# 15_ETHERNET.net
KiCad netlist of a schematic drawn in Altium Designer
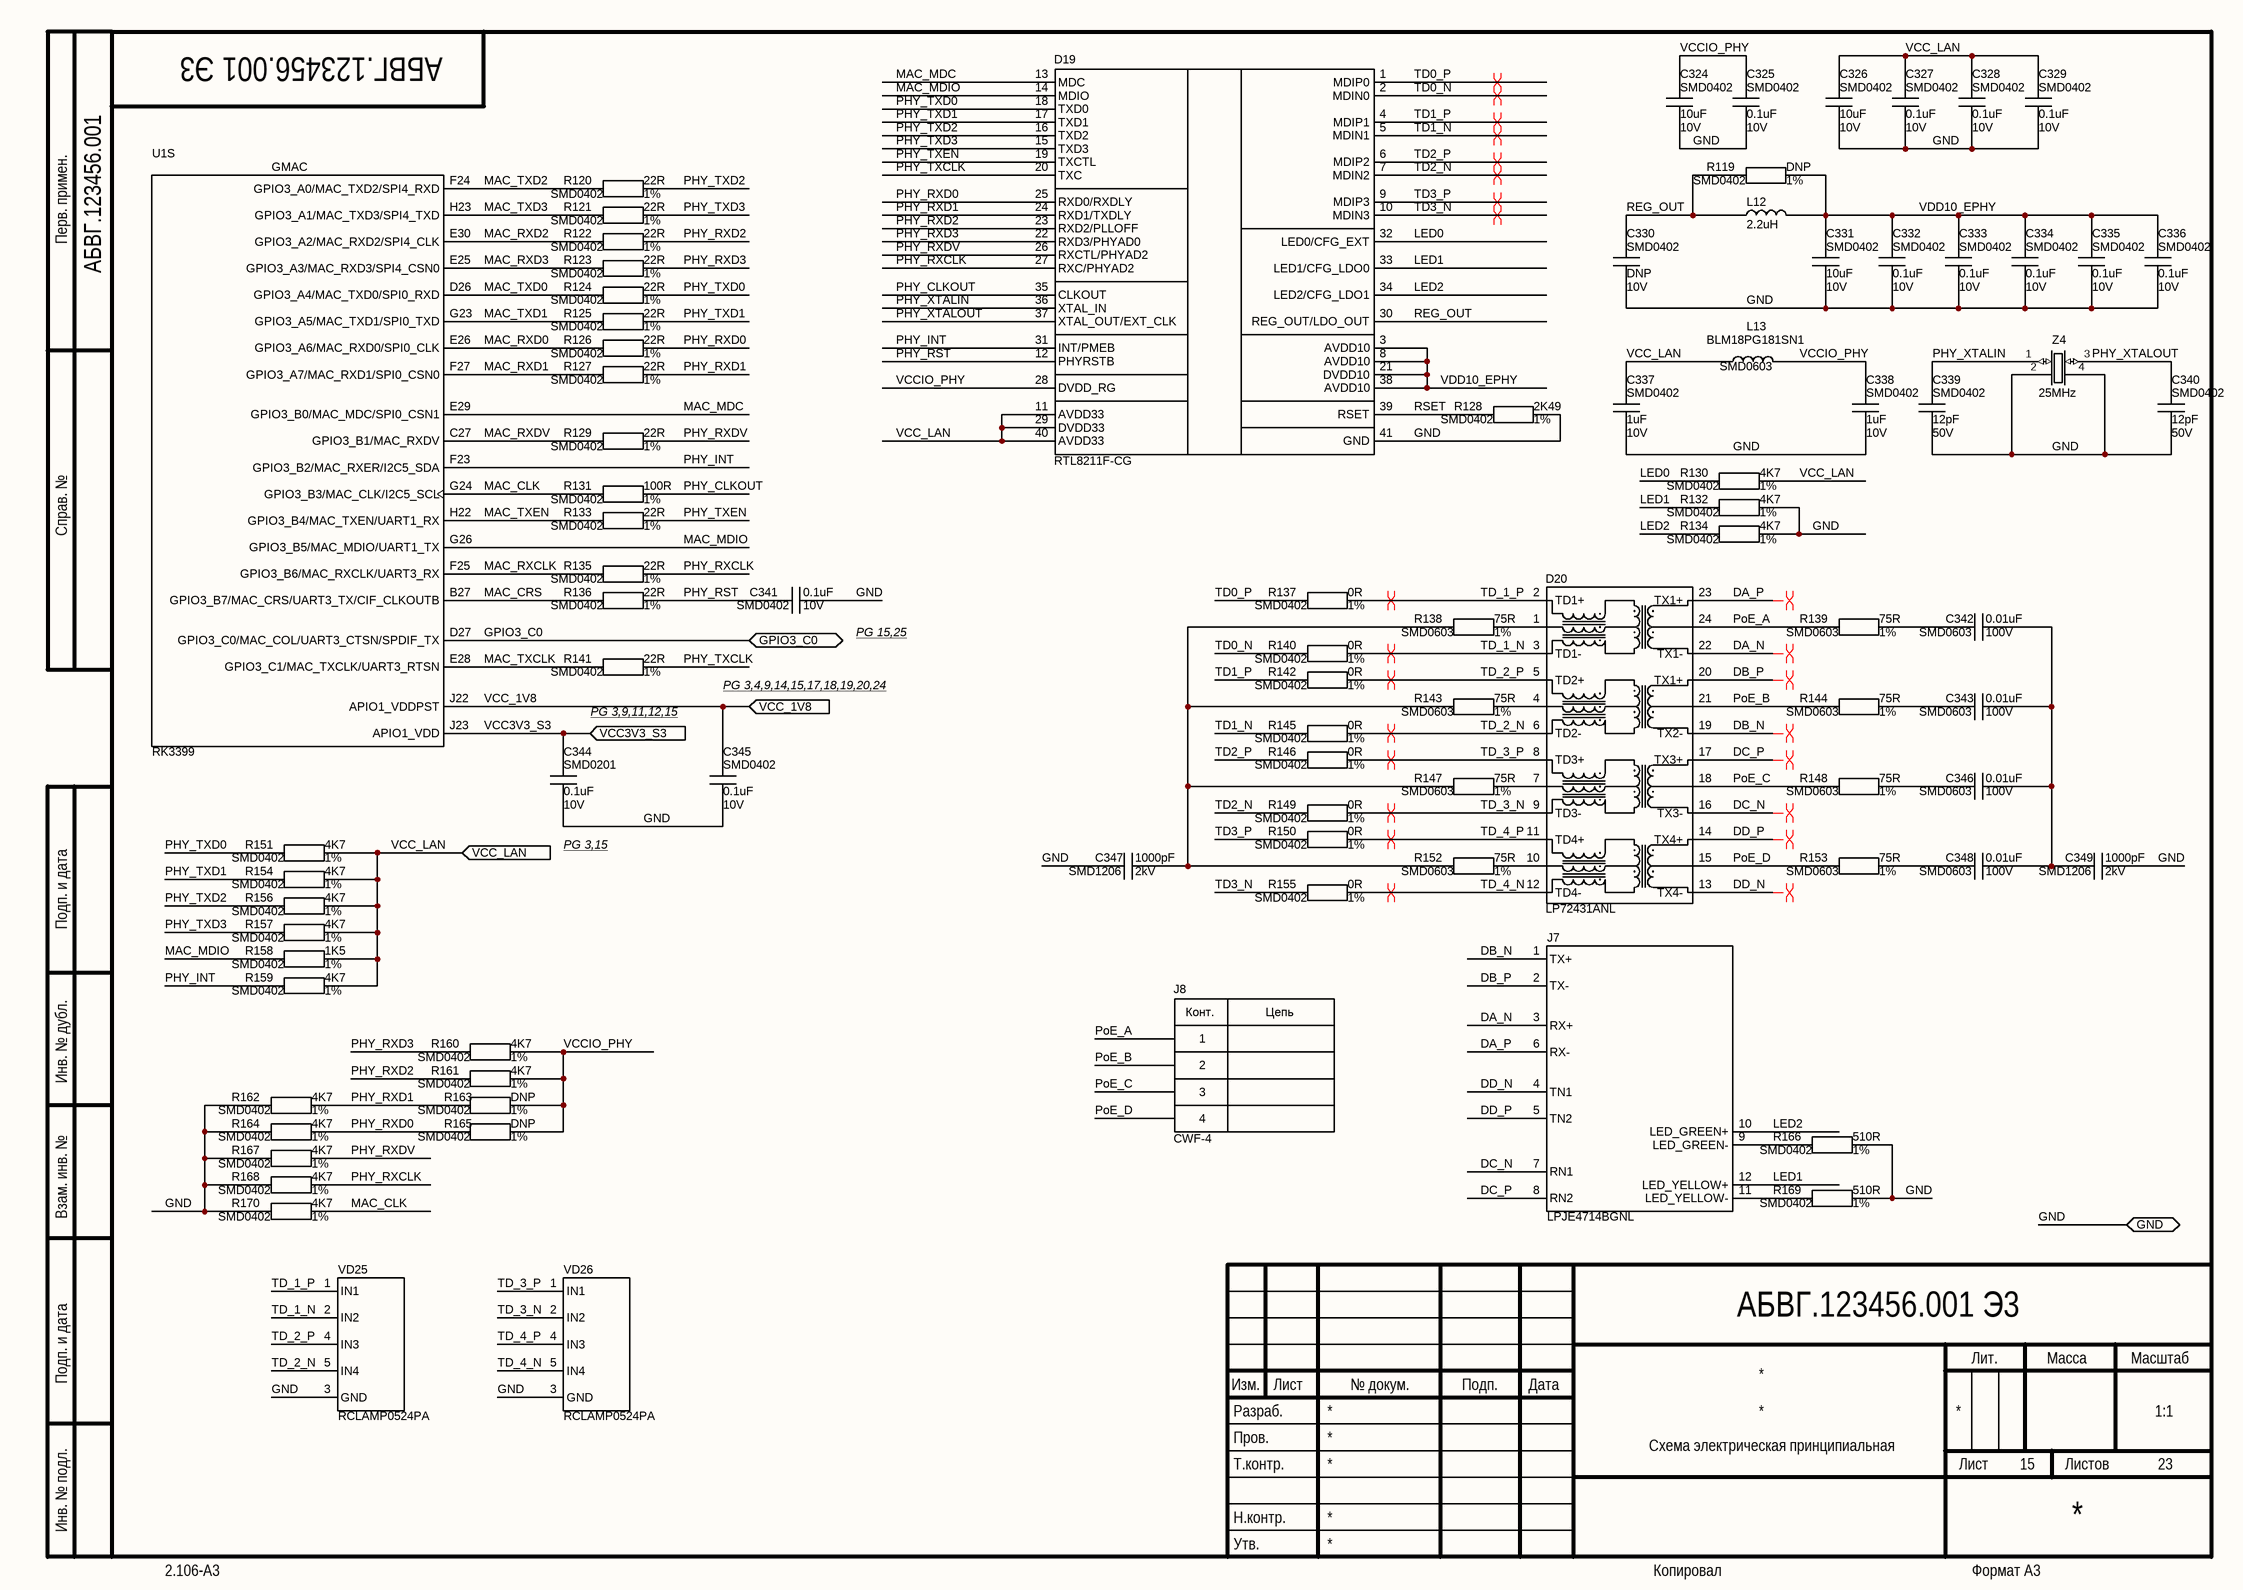
[diagram p0: 15 ETHERNET.SchDoc]

(export (version "E")
  (design (tool "Eeschema 10.0.6"))
  (components
    (comp (ref "C324")
      (value "10uF")
      (footprint "Didur_PcbLib_1:CAP_SMD_0402")
      (fields
        (field (name "PACKAGE") "SMD0402")
        (field (name "PARTNUMBER") "CC0402MRX5R6BB106")
        (field (name "VOLTAGE") "10V")
      )
      (libsource (lib "Didur_SchLib_1") (part "Ceramic_Cap"))
    )
    (comp (ref "C325")
      (value "0.1uF")
      (footprint "Didur_PcbLib_1:CAP_SMD_0402")
      (fields
        (field (name "PACKAGE") "SMD0402")
        (field (name "PARTNUMBER") "CC0402KRX5R6BB104")
        (field (name "VOLTAGE") "10V")
      )
      (libsource (lib "Didur_SchLib_1") (part "Ceramic_Cap"))
    )
    (comp (ref "C326")
      (value "10uF")
      (footprint "Didur_PcbLib_1:CAP_SMD_0402")
      (fields
        (field (name "PACKAGE") "SMD0402")
        (field (name "PARTNUMBER") "CC0402MRX5R6BB106")
        (field (name "VOLTAGE") "10V")
      )
      (libsource (lib "Didur_SchLib_1") (part "Ceramic_Cap"))
    )
    (comp (ref "C327")
      (value "0.1uF")
      (footprint "Didur_PcbLib_1:CAP_SMD_0402")
      (fields
        (field (name "PACKAGE") "SMD0402")
        (field (name "PARTNUMBER") "CC0402KRX5R6BB104")
        (field (name "VOLTAGE") "10V")
      )
      (libsource (lib "Didur_SchLib_1") (part "Ceramic_Cap"))
    )
    (comp (ref "C328")
      (value "0.1uF")
      (footprint "Didur_PcbLib_1:CAP_SMD_0402")
      (fields
        (field (name "PACKAGE") "SMD0402")
        (field (name "PARTNUMBER") "CC0402KRX5R6BB104")
        (field (name "VOLTAGE") "10V")
      )
      (libsource (lib "Didur_SchLib_1") (part "Ceramic_Cap"))
    )
    (comp (ref "C329")
      (value "0.1uF")
      (footprint "Didur_PcbLib_1:CAP_SMD_0402")
      (fields
        (field (name "PACKAGE") "SMD0402")
        (field (name "PARTNUMBER") "CC0402KRX5R6BB104")
        (field (name "VOLTAGE") "10V")
      )
      (libsource (lib "Didur_SchLib_1") (part "Ceramic_Cap"))
    )
    (comp (ref "C330")
      (value "DNP")
      (footprint "Didur_PcbLib_1:CAP_SMD_0402")
      (fields
        (field (name "PACKAGE") "SMD0402")
        (field (name "PARTNUMBER") "CC0402KRX5R6BB104")
        (field (name "VOLTAGE") "10V")
      )
      (libsource (lib "Didur_SchLib_1") (part "Ceramic_Cap"))
    )
    (comp (ref "C331")
      (value "10uF")
      (footprint "Didur_PcbLib_1:CAP_SMD_0402")
      (fields
        (field (name "PACKAGE") "SMD0402")
        (field (name "PARTNUMBER") "CC0402MRX5R6BB106")
        (field (name "VOLTAGE") "10V")
      )
      (libsource (lib "Didur_SchLib_1") (part "Ceramic_Cap"))
    )
    (comp (ref "C332")
      (value "0.1uF")
      (footprint "Didur_PcbLib_1:CAP_SMD_0402")
      (fields
        (field (name "PACKAGE") "SMD0402")
        (field (name "PARTNUMBER") "CC0402KRX5R6BB104")
        (field (name "VOLTAGE") "10V")
      )
      (libsource (lib "Didur_SchLib_1") (part "Ceramic_Cap"))
    )
    (comp (ref "C333")
      (value "0.1uF")
      (footprint "Didur_PcbLib_1:CAP_SMD_0402")
      (fields
        (field (name "PACKAGE") "SMD0402")
        (field (name "PARTNUMBER") "CC0402KRX5R6BB104")
        (field (name "VOLTAGE") "10V")
      )
      (libsource (lib "Didur_SchLib_1") (part "Ceramic_Cap"))
    )
    (comp (ref "C334")
      (value "0.1uF")
      (footprint "Didur_PcbLib_1:CAP_SMD_0402")
      (fields
        (field (name "PACKAGE") "SMD0402")
        (field (name "PARTNUMBER") "CC0402KRX5R6BB104")
        (field (name "VOLTAGE") "10V")
      )
      (libsource (lib "Didur_SchLib_1") (part "Ceramic_Cap"))
    )
    (comp (ref "C335")
      (value "0.1uF")
      (footprint "Didur_PcbLib_1:CAP_SMD_0402")
      (fields
        (field (name "PACKAGE") "SMD0402")
        (field (name "PARTNUMBER") "CC0402KRX5R6BB104")
        (field (name "VOLTAGE") "10V")
      )
      (libsource (lib "Didur_SchLib_1") (part "Ceramic_Cap"))
    )
    (comp (ref "C336")
      (value "0.1uF")
      (footprint "Didur_PcbLib_1:CAP_SMD_0402")
      (fields
        (field (name "PACKAGE") "SMD0402")
        (field (name "PARTNUMBER") "CC0402KRX5R6BB104")
        (field (name "VOLTAGE") "10V")
      )
      (libsource (lib "Didur_SchLib_1") (part "Ceramic_Cap"))
    )
    (comp (ref "C337")
      (value "1uF")
      (footprint "Didur_PcbLib_1:CAP_SMD_0402")
      (fields
        (field (name "PACKAGE") "SMD0402")
        (field (name "PARTNUMBER") "CC0402KRX5R6BB105")
        (field (name "VOLTAGE") "10V")
      )
      (libsource (lib "Didur_SchLib_1") (part "Ceramic_Cap"))
    )
    (comp (ref "C338")
      (value "1uF")
      (footprint "Didur_PcbLib_1:CAP_SMD_0402")
      (fields
        (field (name "PACKAGE") "SMD0402")
        (field (name "PARTNUMBER") "CC0402KRX5R6BB105")
        (field (name "VOLTAGE") "10V")
      )
      (libsource (lib "Didur_SchLib_1") (part "Ceramic_Cap"))
    )
    (comp (ref "C339")
      (value "12pF")
      (footprint "Didur_PcbLib_1:CAP_SMD_0402")
      (fields
        (field (name "PACKAGE") "SMD0402")
        (field (name "PARTNUMBER") "CC0402JRNPO9BN120")
        (field (name "VOLTAGE") "50V")
      )
      (libsource (lib "Didur_SchLib_1") (part "Ceramic_Cap"))
    )
    (comp (ref "C340")
      (value "12pF")
      (footprint "Didur_PcbLib_1:CAP_SMD_0402")
      (fields
        (field (name "PACKAGE") "SMD0402")
        (field (name "PARTNUMBER") "CC0402JRNPO9BN120")
        (field (name "VOLTAGE") "50V")
      )
      (libsource (lib "Didur_SchLib_1") (part "Ceramic_Cap"))
    )
    (comp (ref "C341")
      (value "0.1uF")
      (footprint "Didur_PcbLib_1:CAP_SMD_0402")
      (fields
        (field (name "PACKAGE") "SMD0402")
        (field (name "PARTNUMBER") "CC0402KRX5R6BB104")
        (field (name "VOLTAGE") "10V")
      )
      (libsource (lib "Didur_SchLib_1") (part "Ceramic_Cap"))
    )
    (comp (ref "C342")
      (value "0.01uF")
      (footprint "CAP_SMD_0603")
      (fields
        (field (name "PACKAGE") "SMD0603")
        (field (name "PARTNUMBER") "CC0603KRX7R0BB103")
        (field (name "VOLTAGE") "100V")
      )
      (libsource (lib "Didur_SchLib_1") (part "Ceramic_Cap"))
    )
    (comp (ref "C343")
      (value "0.01uF")
      (footprint "CAP_SMD_0603")
      (fields
        (field (name "PACKAGE") "SMD0603")
        (field (name "PARTNUMBER") "CC0603KRX7R0BB103")
        (field (name "VOLTAGE") "100V")
      )
      (libsource (lib "Didur_SchLib_1") (part "Ceramic_Cap"))
    )
    (comp (ref "C344")
      (value "0.1uF")
      (footprint "Didur_PcbLib_1:CAP_SMD_0201")
      (fields
        (field (name "PACKAGE") "SMD0201")
        (field (name "PARTNUMBER") "CC0201KRX5R6BB104")
        (field (name "VOLTAGE") "10V")
      )
      (libsource (lib "Didur_SchLib_1") (part "Ceramic_Cap"))
    )
    (comp (ref "C345")
      (value "0.1uF")
      (footprint "Didur_PcbLib_1:CAP_SMD_0402")
      (fields
        (field (name "PACKAGE") "SMD0402")
        (field (name "PARTNUMBER") "CC0402KRX5R6BB104")
        (field (name "VOLTAGE") "10V")
      )
      (libsource (lib "Didur_SchLib_1") (part "Ceramic_Cap"))
    )
    (comp (ref "C346")
      (value "0.01uF")
      (footprint "CAP_SMD_0603")
      (fields
        (field (name "PACKAGE") "SMD0603")
        (field (name "PARTNUMBER") "CC0603KRX7R0BB103")
        (field (name "VOLTAGE") "100V")
      )
      (libsource (lib "Didur_SchLib_1") (part "Ceramic_Cap"))
    )
    (comp (ref "C347")
      (value "1000pF")
      (footprint "CAP_SMD_1206")
      (fields
        (field (name "PACKAGE") "SMD1206")
        (field (name "PARTNUMBER") "CC1206MKX7RDBB102")
        (field (name "VOLTAGE") "2kV")
      )
      (libsource (lib "Didur_SchLib_1") (part "Ceramic_Cap"))
    )
    (comp (ref "C348")
      (value "0.01uF")
      (footprint "CAP_SMD_0603")
      (fields
        (field (name "PACKAGE") "SMD0603")
        (field (name "PARTNUMBER") "CC0603KRX7R0BB103")
        (field (name "VOLTAGE") "100V")
      )
      (libsource (lib "Didur_SchLib_1") (part "Ceramic_Cap"))
    )
    (comp (ref "C349")
      (value "1000pF")
      (footprint "CAP_SMD_1206")
      (fields
        (field (name "PACKAGE") "SMD1206")
        (field (name "PARTNUMBER") "CC1206MKX7RDBB102")
        (field (name "VOLTAGE") "2kV")
      )
      (libsource (lib "Didur_SchLib_1") (part "Ceramic_Cap"))
    )
    (comp (ref "D19")
      (value "RTL8211F-CG")
      (footprint "Didur_PcbLib_1:QFN40")
      (libsource (lib "Didur_SchLib_1") (part "RTL8211F-CG"))
    )
    (comp (ref "D20")
      (value "LP72431ANL")
      (footprint "Didur_PcbLib_1:LP72431ANL")
      (libsource (lib "Didur_SchLib_1") (part "LP72431ANL"))
    )
    (comp (ref "J7")
      (value "LPJE4714BGNL")
      (footprint "Didur_PcbLib_1:LPJE4714BGNL")
      (libsource (lib "Didur_SchLib_1") (part "LPJE4714BGNL"))
    )
    (comp (ref "J8")
      (value "CWF-4")
      (footprint "Didur_PcbLib_1:CWF-4")
      (fields (field (name "PARTNUMBER") "DS1069-4MVW6X (CWF-4)"))
      (libsource (lib "Didur_SchLib_1") (part "CON4"))
    )
    (comp (ref "L12")
      (value "2.2uH")
      (footprint "Didur_PcbLib_1:IND_SMD_252012")
      (fields (field (name "PARTNUMBER") "DFE252012P-2R2M=P2") (field (name "Comment") "Value"))
      (libsource (lib "Didur_SchLib_1") (part "Inductor_smal"))
    )
    (comp (ref "L13")
      (value "BLM18PG181SN1")
      (footprint "Didur_PcbLib_1:IND_SMD_0603")
      (fields (field (name "PACKAGE") "SMD0603") (field (name "Comment") "Value"))
      (libsource (lib "Didur_SchLib_1") (part "Inductor_smal"))
    )
    (comp (ref "R119")
      (value "DNP")
      (footprint "Didur_PcbLib_1:RES_SMD_0402")
      (fields
        (field (name "PACKAGE") "SMD0402")
        (field (name "PARTNUMBER") "Do Not Place")
        (field (name "TOLERANCE") "1%")
      )
      (libsource (lib "") (part "Chip_Res_2"))
    )
    (comp (ref "R120")
      (value "22R")
      (footprint "Didur_PcbLib_1:RES_SMD_0402")
      (fields
        (field (name "PACKAGE") "SMD0402")
        (field (name "PARTNUMBER") "RC0402FR-0722RL")
        (field (name "TOLERANCE") "1%")
      )
      (libsource (lib "Didur_SchLib_1") (part "Chip_Res"))
    )
    (comp (ref "R121")
      (value "22R")
      (footprint "Didur_PcbLib_1:RES_SMD_0402")
      (fields
        (field (name "PACKAGE") "SMD0402")
        (field (name "PARTNUMBER") "RC0402FR-0722RL")
        (field (name "TOLERANCE") "1%")
      )
      (libsource (lib "Didur_SchLib_1") (part "Chip_Res"))
    )
    (comp (ref "R122")
      (value "22R")
      (footprint "Didur_PcbLib_1:RES_SMD_0402")
      (fields
        (field (name "PACKAGE") "SMD0402")
        (field (name "PARTNUMBER") "RC0402FR-0722RL")
        (field (name "TOLERANCE") "1%")
      )
      (libsource (lib "Didur_SchLib_1") (part "Chip_Res"))
    )
    (comp (ref "R123")
      (value "22R")
      (footprint "Didur_PcbLib_1:RES_SMD_0402")
      (fields
        (field (name "PACKAGE") "SMD0402")
        (field (name "PARTNUMBER") "RC0402FR-0722RL")
        (field (name "TOLERANCE") "1%")
      )
      (libsource (lib "Didur_SchLib_1") (part "Chip_Res"))
    )
    (comp (ref "R124")
      (value "22R")
      (footprint "Didur_PcbLib_1:RES_SMD_0402")
      (fields
        (field (name "PACKAGE") "SMD0402")
        (field (name "PARTNUMBER") "RC0402FR-0722RL")
        (field (name "TOLERANCE") "1%")
      )
      (libsource (lib "Didur_SchLib_1") (part "Chip_Res"))
    )
    (comp (ref "R125")
      (value "22R")
      (footprint "Didur_PcbLib_1:RES_SMD_0402")
      (fields
        (field (name "PACKAGE") "SMD0402")
        (field (name "PARTNUMBER") "RC0402FR-0722RL")
        (field (name "TOLERANCE") "1%")
      )
      (libsource (lib "Didur_SchLib_1") (part "Chip_Res"))
    )
    (comp (ref "R126")
      (value "22R")
      (footprint "Didur_PcbLib_1:RES_SMD_0402")
      (fields
        (field (name "PACKAGE") "SMD0402")
        (field (name "PARTNUMBER") "RC0402FR-0722RL")
        (field (name "TOLERANCE") "1%")
      )
      (libsource (lib "Didur_SchLib_1") (part "Chip_Res"))
    )
    (comp (ref "R127")
      (value "22R")
      (footprint "Didur_PcbLib_1:RES_SMD_0402")
      (fields
        (field (name "PACKAGE") "SMD0402")
        (field (name "PARTNUMBER") "RC0402FR-0722RL")
        (field (name "TOLERANCE") "1%")
      )
      (libsource (lib "Didur_SchLib_1") (part "Chip_Res"))
    )
    (comp (ref "R128")
      (value "2K49")
      (footprint "Didur_PcbLib_1:RES_SMD_0402")
      (fields
        (field (name "PACKAGE") "SMD0402")
        (field (name "PARTNUMBER") "RC0402FR-072K49L")
        (field (name "TOLERANCE") "1%")
      )
      (libsource (lib "") (part "Chip_Res_1"))
    )
    (comp (ref "R129")
      (value "22R")
      (footprint "Didur_PcbLib_1:RES_SMD_0402")
      (fields
        (field (name "PACKAGE") "SMD0402")
        (field (name "PARTNUMBER") "RC0402FR-0722RL")
        (field (name "TOLERANCE") "1%")
      )
      (libsource (lib "Didur_SchLib_1") (part "Chip_Res"))
    )
    (comp (ref "R130")
      (value "4K7")
      (footprint "Didur_PcbLib_1:RES_SMD_0402")
      (fields
        (field (name "PACKAGE") "SMD0402")
        (field (name "PARTNUMBER") "RC0402FR-074K7L")
        (field (name "TOLERANCE") "1%")
      )
      (libsource (lib "") (part "Chip_Res_1"))
    )
    (comp (ref "R131")
      (value "100R")
      (footprint "Didur_PcbLib_1:RES_SMD_0402")
      (fields
        (field (name "PACKAGE") "SMD0402")
        (field (name "PARTNUMBER") "RC0402FR-07100RL")
        (field (name "TOLERANCE") "1%")
      )
      (libsource (lib "") (part "Chip_Res_1"))
    )
    (comp (ref "R132")
      (value "4K7")
      (footprint "Didur_PcbLib_1:RES_SMD_0402")
      (fields
        (field (name "PACKAGE") "SMD0402")
        (field (name "PARTNUMBER") "RC0402FR-074K7L")
        (field (name "TOLERANCE") "1%")
      )
      (libsource (lib "") (part "Chip_Res_1"))
    )
    (comp (ref "R133")
      (value "22R")
      (footprint "Didur_PcbLib_1:RES_SMD_0402")
      (fields
        (field (name "PACKAGE") "SMD0402")
        (field (name "PARTNUMBER") "RC0402FR-0722RL")
        (field (name "TOLERANCE") "1%")
      )
      (libsource (lib "Didur_SchLib_1") (part "Chip_Res"))
    )
    (comp (ref "R134")
      (value "4K7")
      (footprint "Didur_PcbLib_1:RES_SMD_0402")
      (fields
        (field (name "PACKAGE") "SMD0402")
        (field (name "PARTNUMBER") "RC0402FR-074K7L")
        (field (name "TOLERANCE") "1%")
      )
      (libsource (lib "") (part "Chip_Res_1"))
    )
    (comp (ref "R135")
      (value "22R")
      (footprint "Didur_PcbLib_1:RES_SMD_0402")
      (fields
        (field (name "PACKAGE") "SMD0402")
        (field (name "PARTNUMBER") "RC0402FR-0722RL")
        (field (name "TOLERANCE") "1%")
      )
      (libsource (lib "Didur_SchLib_1") (part "Chip_Res"))
    )
    (comp (ref "R136")
      (value "22R")
      (footprint "Didur_PcbLib_1:RES_SMD_0402")
      (fields
        (field (name "PACKAGE") "SMD0402")
        (field (name "PARTNUMBER") "RC0402FR-0722RL")
        (field (name "TOLERANCE") "1%")
      )
      (libsource (lib "Didur_SchLib_1") (part "Chip_Res"))
    )
    (comp (ref "R137")
      (value "0R")
      (footprint "Didur_PcbLib_1:RES_SMD_0402")
      (fields
        (field (name "PACKAGE") "SMD0402")
        (field (name "PARTNUMBER") "RC0402FR-070RL")
        (field (name "TOLERANCE") "1%")
      )
      (libsource (lib "") (part "Chip_Res_1"))
    )
    (comp (ref "R138")
      (value "75R")
      (footprint "RES_SMD_0603")
      (fields
        (field (name "PACKAGE") "SMD0603")
        (field (name "PARTNUMBER") "RC0603FR-0775RL")
        (field (name "TOLERANCE") "1%")
      )
      (libsource (lib "") (part "Chip_Res_3"))
    )
    (comp (ref "R139")
      (value "75R")
      (footprint "RES_SMD_0603")
      (fields
        (field (name "PACKAGE") "SMD0603")
        (field (name "PARTNUMBER") "RC0603FR-0775RL")
        (field (name "TOLERANCE") "1%")
      )
      (libsource (lib "") (part "Chip_Res_2"))
    )
    (comp (ref "R140")
      (value "0R")
      (footprint "Didur_PcbLib_1:RES_SMD_0402")
      (fields
        (field (name "PACKAGE") "SMD0402")
        (field (name "PARTNUMBER") "RC0402FR-070RL")
        (field (name "TOLERANCE") "1%")
      )
      (libsource (lib "") (part "Chip_Res_1"))
    )
    (comp (ref "R141")
      (value "22R")
      (footprint "Didur_PcbLib_1:RES_SMD_0402")
      (fields
        (field (name "PACKAGE") "SMD0402")
        (field (name "PARTNUMBER") "RC0402FR-0722RL")
        (field (name "TOLERANCE") "1%")
      )
      (libsource (lib "Didur_SchLib_1") (part "Chip_Res"))
    )
    (comp (ref "R142")
      (value "0R")
      (footprint "Didur_PcbLib_1:RES_SMD_0402")
      (fields
        (field (name "PACKAGE") "SMD0402")
        (field (name "PARTNUMBER") "RC0402FR-070RL")
        (field (name "TOLERANCE") "1%")
      )
      (libsource (lib "") (part "Chip_Res_1"))
    )
    (comp (ref "R143")
      (value "75R")
      (footprint "RES_SMD_0603")
      (fields
        (field (name "PACKAGE") "SMD0603")
        (field (name "PARTNUMBER") "RC0603FR-0775RL")
        (field (name "TOLERANCE") "1%")
      )
      (libsource (lib "") (part "Chip_Res_3"))
    )
    (comp (ref "R144")
      (value "75R")
      (footprint "RES_SMD_0603")
      (fields
        (field (name "PACKAGE") "SMD0603")
        (field (name "PARTNUMBER") "RC0603FR-0775RL")
        (field (name "TOLERANCE") "1%")
      )
      (libsource (lib "") (part "Chip_Res_2"))
    )
    (comp (ref "R145")
      (value "0R")
      (footprint "Didur_PcbLib_1:RES_SMD_0402")
      (fields
        (field (name "PACKAGE") "SMD0402")
        (field (name "PARTNUMBER") "RC0402FR-070RL")
        (field (name "TOLERANCE") "1%")
      )
      (libsource (lib "") (part "Chip_Res_1"))
    )
    (comp (ref "R146")
      (value "0R")
      (footprint "Didur_PcbLib_1:RES_SMD_0402")
      (fields
        (field (name "PACKAGE") "SMD0402")
        (field (name "PARTNUMBER") "RC0402FR-070RL")
        (field (name "TOLERANCE") "1%")
      )
      (libsource (lib "") (part "Chip_Res_1"))
    )
    (comp (ref "R147")
      (value "75R")
      (footprint "RES_SMD_0603")
      (fields
        (field (name "PACKAGE") "SMD0603")
        (field (name "PARTNUMBER") "RC0603FR-0775RL")
        (field (name "TOLERANCE") "1%")
      )
      (libsource (lib "") (part "Chip_Res_3"))
    )
    (comp (ref "R148")
      (value "75R")
      (footprint "RES_SMD_0603")
      (fields
        (field (name "PACKAGE") "SMD0603")
        (field (name "PARTNUMBER") "RC0603FR-0775RL")
        (field (name "TOLERANCE") "1%")
      )
      (libsource (lib "") (part "Chip_Res_2"))
    )
    (comp (ref "R149")
      (value "0R")
      (footprint "Didur_PcbLib_1:RES_SMD_0402")
      (fields
        (field (name "PACKAGE") "SMD0402")
        (field (name "PARTNUMBER") "RC0402FR-070RL")
        (field (name "TOLERANCE") "1%")
      )
      (libsource (lib "") (part "Chip_Res_1"))
    )
    (comp (ref "R150")
      (value "0R")
      (footprint "Didur_PcbLib_1:RES_SMD_0402")
      (fields
        (field (name "PACKAGE") "SMD0402")
        (field (name "PARTNUMBER") "RC0402FR-070RL")
        (field (name "TOLERANCE") "1%")
      )
      (libsource (lib "") (part "Chip_Res_1"))
    )
    (comp (ref "R151")
      (value "4K7")
      (footprint "Didur_PcbLib_1:RES_SMD_0402")
      (fields
        (field (name "PACKAGE") "SMD0402")
        (field (name "PARTNUMBER") "RC0402FR-074K7L")
        (field (name "TOLERANCE") "1%")
      )
      (libsource (lib "") (part "Chip_Res_1"))
    )
    (comp (ref "R152")
      (value "75R")
      (footprint "RES_SMD_0603")
      (fields
        (field (name "PACKAGE") "SMD0603")
        (field (name "PARTNUMBER") "RC0603FR-0775RL")
        (field (name "TOLERANCE") "1%")
      )
      (libsource (lib "") (part "Chip_Res_3"))
    )
    (comp (ref "R153")
      (value "75R")
      (footprint "RES_SMD_0603")
      (fields
        (field (name "PACKAGE") "SMD0603")
        (field (name "PARTNUMBER") "RC0603FR-0775RL")
        (field (name "TOLERANCE") "1%")
      )
      (libsource (lib "") (part "Chip_Res_2"))
    )
    (comp (ref "R154")
      (value "4K7")
      (footprint "Didur_PcbLib_1:RES_SMD_0402")
      (fields
        (field (name "PACKAGE") "SMD0402")
        (field (name "PARTNUMBER") "RC0402FR-074K7L")
        (field (name "TOLERANCE") "1%")
      )
      (libsource (lib "") (part "Chip_Res_1"))
    )
    (comp (ref "R155")
      (value "0R")
      (footprint "Didur_PcbLib_1:RES_SMD_0402")
      (fields
        (field (name "PACKAGE") "SMD0402")
        (field (name "PARTNUMBER") "RC0402FR-070RL")
        (field (name "TOLERANCE") "1%")
      )
      (libsource (lib "") (part "Chip_Res_1"))
    )
    (comp (ref "R156")
      (value "4K7")
      (footprint "Didur_PcbLib_1:RES_SMD_0402")
      (fields
        (field (name "PACKAGE") "SMD0402")
        (field (name "PARTNUMBER") "RC0402FR-074K7L")
        (field (name "TOLERANCE") "1%")
      )
      (libsource (lib "") (part "Chip_Res_1"))
    )
    (comp (ref "R157")
      (value "4K7")
      (footprint "Didur_PcbLib_1:RES_SMD_0402")
      (fields
        (field (name "PACKAGE") "SMD0402")
        (field (name "PARTNUMBER") "RC0402FR-074K7L")
        (field (name "TOLERANCE") "1%")
      )
      (libsource (lib "") (part "Chip_Res_1"))
    )
    (comp (ref "R158")
      (value "1K5")
      (footprint "Didur_PcbLib_1:RES_SMD_0402")
      (fields
        (field (name "PACKAGE") "SMD0402")
        (field (name "PARTNUMBER") "RC0402FR-071K5L")
        (field (name "TOLERANCE") "1%")
      )
      (libsource (lib "") (part "Chip_Res_1"))
    )
    (comp (ref "R159")
      (value "4K7")
      (footprint "Didur_PcbLib_1:RES_SMD_0402")
      (fields
        (field (name "PACKAGE") "SMD0402")
        (field (name "PARTNUMBER") "RC0402FR-074K7L")
        (field (name "TOLERANCE") "1%")
      )
      (libsource (lib "") (part "Chip_Res_1"))
    )
    (comp (ref "R160")
      (value "4K7")
      (footprint "Didur_PcbLib_1:RES_SMD_0402")
      (fields
        (field (name "PACKAGE") "SMD0402")
        (field (name "PARTNUMBER") "RC0402FR-074K7L")
        (field (name "TOLERANCE") "1%")
      )
      (libsource (lib "") (part "Chip_Res_1"))
    )
    (comp (ref "R161")
      (value "4K7")
      (footprint "Didur_PcbLib_1:RES_SMD_0402")
      (fields
        (field (name "PACKAGE") "SMD0402")
        (field (name "PARTNUMBER") "RC0402FR-074K7L")
        (field (name "TOLERANCE") "1%")
      )
      (libsource (lib "") (part "Chip_Res_1"))
    )
    (comp (ref "R162")
      (value "4K7")
      (footprint "Didur_PcbLib_1:RES_SMD_0402")
      (fields
        (field (name "PACKAGE") "SMD0402")
        (field (name "PARTNUMBER") "RC0402FR-074K7L")
        (field (name "TOLERANCE") "1%")
      )
      (libsource (lib "") (part "Chip_Res_1"))
    )
    (comp (ref "R163")
      (value "DNP")
      (footprint "Didur_PcbLib_1:RES_SMD_0402")
      (fields
        (field (name "PACKAGE") "SMD0402")
        (field (name "PARTNUMBER") "Do Not Place")
        (field (name "TOLERANCE") "1%")
      )
      (libsource (lib "") (part "Chip_Res_2"))
    )
    (comp (ref "R164")
      (value "4K7")
      (footprint "Didur_PcbLib_1:RES_SMD_0402")
      (fields
        (field (name "PACKAGE") "SMD0402")
        (field (name "PARTNUMBER") "RC0402FR-074K7L")
        (field (name "TOLERANCE") "1%")
      )
      (libsource (lib "") (part "Chip_Res_1"))
    )
    (comp (ref "R165")
      (value "DNP")
      (footprint "Didur_PcbLib_1:RES_SMD_0402")
      (fields
        (field (name "PACKAGE") "SMD0402")
        (field (name "PARTNUMBER") "Do Not Place")
        (field (name "TOLERANCE") "1%")
      )
      (libsource (lib "") (part "Chip_Res_2"))
    )
    (comp (ref "R166")
      (value "510R")
      (footprint "Didur_PcbLib_1:RES_SMD_0402")
      (fields
        (field (name "PACKAGE") "SMD0402")
        (field (name "PARTNUMBER") "RC0402FR-07510RL")
        (field (name "TOLERANCE") "1%")
      )
      (libsource (lib "") (part "Chip_Res_1"))
    )
    (comp (ref "R167")
      (value "4K7")
      (footprint "Didur_PcbLib_1:RES_SMD_0402")
      (fields
        (field (name "PACKAGE") "SMD0402")
        (field (name "PARTNUMBER") "RC0402FR-074K7L")
        (field (name "TOLERANCE") "1%")
      )
      (libsource (lib "") (part "Chip_Res_1"))
    )
    (comp (ref "R168")
      (value "4K7")
      (footprint "Didur_PcbLib_1:RES_SMD_0402")
      (fields
        (field (name "PACKAGE") "SMD0402")
        (field (name "PARTNUMBER") "RC0402FR-074K7L")
        (field (name "TOLERANCE") "1%")
      )
      (libsource (lib "") (part "Chip_Res_1"))
    )
    (comp (ref "R169")
      (value "510R")
      (footprint "Didur_PcbLib_1:RES_SMD_0402")
      (fields
        (field (name "PACKAGE") "SMD0402")
        (field (name "PARTNUMBER") "RC0402FR-07510RL")
        (field (name "TOLERANCE") "1%")
      )
      (libsource (lib "") (part "Chip_Res_1"))
    )
    (comp (ref "R170")
      (value "4K7")
      (footprint "Didur_PcbLib_1:RES_SMD_0402")
      (fields
        (field (name "PACKAGE") "SMD0402")
        (field (name "PARTNUMBER") "RC0402FR-074K7L")
        (field (name "TOLERANCE") "1%")
      )
      (libsource (lib "") (part "Chip_Res_1"))
    )
    (comp (ref "U1")
      (value "RK3399")
      (footprint "BGA828C65P31X31_2100X2100X161N")
      (fields (field (name "Comment") "RK3399_FF"))
      (libsource (lib "Didur_SchLib_1") (part "RK3399_FF"))
    )
    (comp (ref "VD25")
      (value "RCLAMP0524PA")
      (footprint "Didur_PcbLib_1:RCLAMP0524PA")
      (libsource (lib "Didur_SchLib_1") (part "RCLAMP0524PA"))
    )
    (comp (ref "VD26")
      (value "RCLAMP0524PA")
      (footprint "Didur_PcbLib_1:RCLAMP0524PA")
      (libsource (lib "Didur_SchLib_1") (part "RCLAMP0524PA"))
    )
    (comp (ref "Z4")
      (value "25MHz")
      (footprint "Didur_PcbLib_1:TSX3225")
      (fields (field (name "PARTNUMBER") "X322525MOB4SI") (field (name "Comment") "Value"))
      (libsource (lib "Didur_SchLib_1") (part "OSC3225"))
    )
  )
  (nets
    (net (code "1") (name "/DA_N") (class "Default")
      (node (ref "D20") (pin "22") (pinfunction "TX1-_22") (pintype "passive"))
      (node (ref "J7") (pin "3") (pinfunction "RX+_3") (pintype "passive"))
    )
    (net (code "2") (name "/DA_P") (class "Default")
      (node (ref "D20") (pin "23") (pinfunction "TX1+_23") (pintype "passive"))
      (node (ref "J7") (pin "6") (pinfunction "RX-_6") (pintype "passive"))
    )
    (net (code "3") (name "/DB_N") (class "Default")
      (node (ref "D20") (pin "19") (pinfunction "TX2-_19") (pintype "passive"))
      (node (ref "J7") (pin "1") (pinfunction "TX+_1") (pintype "passive"))
    )
    (net (code "4") (name "/DB_P") (class "Default")
      (node (ref "D20") (pin "20") (pinfunction "TX1+_20") (pintype "passive"))
      (node (ref "J7") (pin "2") (pinfunction "TX-_2") (pintype "passive"))
    )
    (net (code "5") (name "/DC_N") (class "Default")
      (node (ref "D20") (pin "16") (pinfunction "TX3-_16") (pintype "passive"))
      (node (ref "J7") (pin "7") (pinfunction "RN1_7") (pintype "passive"))
    )
    (net (code "6") (name "/DC_P") (class "Default")
      (node (ref "D20") (pin "17") (pinfunction "TX3+_17") (pintype "passive"))
      (node (ref "J7") (pin "8") (pinfunction "RN2_8") (pintype "passive"))
    )
    (net (code "7") (name "/DD_N") (class "Default")
      (node (ref "D20") (pin "13") (pinfunction "TX4-_13") (pintype "passive"))
      (node (ref "J7") (pin "4") (pinfunction "TN1_4") (pintype "passive"))
    )
    (net (code "8") (name "/DD_P") (class "Default")
      (node (ref "D20") (pin "14") (pinfunction "TX4+_14") (pintype "passive"))
      (node (ref "J7") (pin "5") (pinfunction "TN2_5") (pintype "passive"))
    )
    (net (code "9") (name "/GND") (class "Default")
      (node (ref "C324") (pin "2") (pinfunction "2_2") (pintype "power_in"))
      (node (ref "C325") (pin "2") (pinfunction "2_2") (pintype "power_in"))
      (node (ref "C326") (pin "2") (pinfunction "2_2") (pintype "power_in"))
      (node (ref "C327") (pin "2") (pinfunction "2_2") (pintype "power_in"))
      (node (ref "C328") (pin "2") (pinfunction "2_2") (pintype "power_in"))
      (node (ref "C329") (pin "2") (pinfunction "2_2") (pintype "power_in"))
      (node (ref "C330") (pin "2") (pinfunction "2_2") (pintype "power_in"))
      (node (ref "C331") (pin "2") (pinfunction "2_2") (pintype "power_in"))
      (node (ref "C332") (pin "2") (pinfunction "2_2") (pintype "power_in"))
      (node (ref "C333") (pin "2") (pinfunction "2_2") (pintype "power_in"))
      (node (ref "C334") (pin "2") (pinfunction "2_2") (pintype "power_in"))
      (node (ref "C335") (pin "2") (pinfunction "2_2") (pintype "power_in"))
      (node (ref "C336") (pin "2") (pinfunction "2_2") (pintype "power_in"))
      (node (ref "C337") (pin "2") (pinfunction "2_2") (pintype "power_in"))
      (node (ref "C338") (pin "2") (pinfunction "2_2") (pintype "power_in"))
      (node (ref "C339") (pin "2") (pinfunction "2_2") (pintype "power_in"))
      (node (ref "C340") (pin "2") (pinfunction "2_2") (pintype "power_in"))
      (node (ref "C341") (pin "2") (pinfunction "2_2") (pintype "power_in"))
      (node (ref "C344") (pin "2") (pinfunction "2_2") (pintype "power_in"))
      (node (ref "C345") (pin "2") (pinfunction "2_2") (pintype "power_in"))
      (node (ref "C347") (pin "2") (pinfunction "2_2") (pintype "power_in"))
      (node (ref "C349") (pin "1") (pinfunction "1_1") (pintype "power_in"))
      (node (ref "D19") (pin "41") (pinfunction "GND_41") (pintype "passive"))
      (node (ref "R128") (pin "2") (pinfunction "2_2") (pintype "passive"))
      (node (ref "R132") (pin "2") (pinfunction "2_2") (pintype "passive"))
      (node (ref "R134") (pin "2") (pinfunction "2_2") (pintype "passive"))
      (node (ref "R162") (pin "1") (pinfunction "1_1") (pintype "passive"))
      (node (ref "R164") (pin "1") (pinfunction "1_1") (pintype "passive"))
      (node (ref "R166") (pin "2") (pinfunction "2_2") (pintype "passive"))
      (node (ref "R167") (pin "1") (pinfunction "1_1") (pintype "passive"))
      (node (ref "R168") (pin "1") (pinfunction "1_1") (pintype "passive"))
      (node (ref "R169") (pin "2") (pinfunction "2_2") (pintype "passive"))
      (node (ref "R170") (pin "1") (pinfunction "1_1") (pintype "passive"))
      (node (ref "VD25") (pin "3") (pinfunction "GND_3") (pintype "passive"))
      (node (ref "VD26") (pin "3") (pinfunction "GND_3") (pintype "passive"))
      (node (ref "Z4") (pin "2") (pinfunction "GND_2") (pintype "passive"))
      (node (ref "Z4") (pin "4") (pinfunction "GND_4") (pintype "passive"))
    )
    (net (code "10") (name "/GPIO3_C0") (class "Default")
      (node (ref "U1") (pin "D27") (pinfunction "GPIO3_C0/MAC_COL/UART3_CTSN/SPDIF_TX_D27") (pintype "passive"))
    )
    (net (code "11") (name "/LED0") (class "Default")
      (node (ref "D19") (pin "32") (pinfunction "LED0/CFG_EXT_32") (pintype "passive"))
      (node (ref "R130") (pin "1") (pinfunction "1_1") (pintype "passive"))
    )
    (net (code "12") (name "/LED1") (class "Default")
      (node (ref "D19") (pin "33") (pinfunction "LED1/CFG_LDO0_33") (pintype "passive"))
      (node (ref "J7") (pin "12") (pinfunction "LED_YELLOW+_12") (pintype "passive"))
      (node (ref "R132") (pin "1") (pinfunction "1_1") (pintype "passive"))
    )
    (net (code "13") (name "/LED2") (class "Default")
      (node (ref "D19") (pin "34") (pinfunction "LED2/CFG_LDO1_34") (pintype "passive"))
      (node (ref "J7") (pin "10") (pinfunction "LED_GREEN+_10") (pintype "passive"))
      (node (ref "R134") (pin "1") (pinfunction "1_1") (pintype "passive"))
    )
    (net (code "14") (name "/MAC_CLK") (class "Default")
      (node (ref "R131") (pin "1") (pinfunction "1_1") (pintype "passive"))
      (node (ref "R170") (pin "2") (pinfunction "2_2") (pintype "passive"))
      (node (ref "U1") (pin "G24") (pinfunction "GPIO3_B3/MAC_CLK/I2C5_SCL_G24") (pintype "passive"))
    )
    (net (code "15") (name "/MAC_CRS") (class "Default")
      (node (ref "R136") (pin "2") (pinfunction "2_2") (pintype "passive"))
      (node (ref "U1") (pin "B27") (pinfunction "GPIO3_B7/MAC_CRS/UART3_TX/CIF_CLKOUTB_B27") (pintype "passive"))
    )
    (net (code "16") (name "/MAC_MDC") (class "Default")
      (node (ref "D19") (pin "13") (pinfunction "MDC_13") (pintype "passive"))
      (node (ref "U1") (pin "E29") (pinfunction "GPIO3_B0/MAC_MDC/SPI0_CSN1_E29") (pintype "passive"))
    )
    (net (code "17") (name "/MAC_MDIO") (class "Default")
      (node (ref "D19") (pin "14") (pinfunction "MDIO_14") (pintype "passive"))
      (node (ref "R158") (pin "1") (pinfunction "1_1") (pintype "passive"))
      (node (ref "U1") (pin "G26") (pinfunction "GPIO3_B5/MAC_MDIO/UART1_TX_G26") (pintype "passive"))
    )
    (net (code "18") (name "/MAC_RXCLK") (class "Default")
      (node (ref "R135") (pin "2") (pinfunction "2_2") (pintype "passive"))
      (node (ref "U1") (pin "F25") (pinfunction "GPIO3_B6/MAC_RXCLK/UART3_RX_F25") (pintype "passive"))
    )
    (net (code "19") (name "/MAC_RXD0") (class "Default")
      (node (ref "R126") (pin "2") (pinfunction "2_2") (pintype "passive"))
      (node (ref "U1") (pin "E26") (pinfunction "GPIO3_A6/MAC_RXD0/SPI0_CLK_E26") (pintype "passive"))
    )
    (net (code "20") (name "/MAC_RXD1") (class "Default")
      (node (ref "R127") (pin "2") (pinfunction "2_2") (pintype "passive"))
      (node (ref "U1") (pin "F27") (pinfunction "GPIO3_A7/MAC_RXD1/SPI0_CSN0_F27") (pintype "passive"))
    )
    (net (code "21") (name "/MAC_RXD2") (class "Default")
      (node (ref "R122") (pin "2") (pinfunction "2_2") (pintype "passive"))
      (node (ref "U1") (pin "E30") (pinfunction "GPIO3_A2/MAC_RXD2/SPI4_CLK_E30") (pintype "passive"))
    )
    (net (code "22") (name "/MAC_RXD3") (class "Default")
      (node (ref "R123") (pin "2") (pinfunction "2_2") (pintype "passive"))
      (node (ref "U1") (pin "E25") (pinfunction "GPIO3_A3/MAC_RXD3/SPI4_CSN0_E25") (pintype "passive"))
    )
    (net (code "23") (name "/MAC_RXDV") (class "Default")
      (node (ref "R129") (pin "2") (pinfunction "2_2") (pintype "passive"))
      (node (ref "U1") (pin "C27") (pinfunction "GPIO3_B1/MAC_RXDV_C27") (pintype "passive"))
    )
    (net (code "24") (name "/MAC_TXCLK") (class "Default")
      (node (ref "R141") (pin "2") (pinfunction "2_2") (pintype "passive"))
      (node (ref "U1") (pin "E28") (pinfunction "GPIO3_C1/MAC_TXCLK/UART3_RTSN_E28") (pintype "passive"))
    )
    (net (code "25") (name "/MAC_TXD0") (class "Default")
      (node (ref "R124") (pin "2") (pinfunction "2_2") (pintype "passive"))
      (node (ref "U1") (pin "D26") (pinfunction "GPIO3_A4/MAC_TXD0/SPI0_RXD_D26") (pintype "passive"))
    )
    (net (code "26") (name "/MAC_TXD1") (class "Default")
      (node (ref "R125") (pin "2") (pinfunction "2_2") (pintype "passive"))
      (node (ref "U1") (pin "G23") (pinfunction "GPIO3_A5/MAC_TXD1/SPI0_TXD_G23") (pintype "passive"))
    )
    (net (code "27") (name "/MAC_TXD2") (class "Default")
      (node (ref "R120") (pin "2") (pinfunction "2_2") (pintype "passive"))
      (node (ref "U1") (pin "F24") (pinfunction "GPIO3_A0/MAC_TXD2/SPI4_RXD_F24") (pintype "passive"))
    )
    (net (code "28") (name "/MAC_TXD3") (class "Default")
      (node (ref "R121") (pin "2") (pinfunction "2_2") (pintype "passive"))
      (node (ref "U1") (pin "H23") (pinfunction "GPIO3_A1/MAC_TXD3/SPI4_TXD_H23") (pintype "passive"))
    )
    (net (code "29") (name "/MAC_TXEN") (class "Default")
      (node (ref "R133") (pin "2") (pinfunction "2_2") (pintype "passive"))
      (node (ref "U1") (pin "H22") (pinfunction "GPIO3_B4/MAC_TXEN/UART1_RX_H22") (pintype "passive"))
    )
    (net (code "30") (name "/PHY_CLKOUT") (class "Default")
      (node (ref "D19") (pin "35") (pinfunction "CLKOUT_35") (pintype "passive"))
      (node (ref "R131") (pin "2") (pinfunction "2_2") (pintype "passive"))
    )
    (net (code "31") (name "/PHY_INT") (class "Default")
      (node (ref "D19") (pin "31") (pinfunction "INT/PMEB_31") (pintype "passive"))
      (node (ref "R159") (pin "1") (pinfunction "1_1") (pintype "passive"))
      (node (ref "U1") (pin "F23") (pinfunction "GPIO3_B2/MAC_RXER/I2C5_SDA_F23") (pintype "passive"))
    )
    (net (code "32") (name "/PHY_RST") (class "Default")
      (node (ref "C341") (pin "1") (pinfunction "1_1") (pintype "power_in"))
      (node (ref "D19") (pin "12") (pinfunction "PHYRSTB_12") (pintype "passive"))
      (node (ref "R136") (pin "1") (pinfunction "1_1") (pintype "passive"))
    )
    (net (code "33") (name "/PHY_RXCLK") (class "Default")
      (node (ref "D19") (pin "27") (pinfunction "RXC/PHYAD2_27") (pintype "passive"))
      (node (ref "R135") (pin "1") (pinfunction "1_1") (pintype "passive"))
      (node (ref "R168") (pin "2") (pinfunction "2_2") (pintype "passive"))
    )
    (net (code "34") (name "/PHY_RXD0") (class "Default")
      (node (ref "D19") (pin "25") (pinfunction "RXD0/RXDLY_25") (pintype "passive"))
      (node (ref "R126") (pin "1") (pinfunction "1_1") (pintype "passive"))
      (node (ref "R164") (pin "2") (pinfunction "2_2") (pintype "passive"))
      (node (ref "R165") (pin "1") (pinfunction "1_1") (pintype "passive"))
    )
    (net (code "35") (name "/PHY_RXD1") (class "Default")
      (node (ref "D19") (pin "24") (pinfunction "RXD1/TXDLY_24") (pintype "passive"))
      (node (ref "R127") (pin "1") (pinfunction "1_1") (pintype "passive"))
      (node (ref "R162") (pin "2") (pinfunction "2_2") (pintype "passive"))
      (node (ref "R163") (pin "1") (pinfunction "1_1") (pintype "passive"))
    )
    (net (code "36") (name "/PHY_RXD2") (class "Default")
      (node (ref "D19") (pin "23") (pinfunction "RXD2/PLLOFF_23") (pintype "passive"))
      (node (ref "R122") (pin "1") (pinfunction "1_1") (pintype "passive"))
      (node (ref "R161") (pin "1") (pinfunction "1_1") (pintype "passive"))
    )
    (net (code "37") (name "/PHY_RXD3") (class "Default")
      (node (ref "D19") (pin "22") (pinfunction "RXD3/PHYAD0_22") (pintype "passive"))
      (node (ref "R123") (pin "1") (pinfunction "1_1") (pintype "passive"))
      (node (ref "R160") (pin "1") (pinfunction "1_1") (pintype "passive"))
    )
    (net (code "38") (name "/PHY_RXDV") (class "Default")
      (node (ref "D19") (pin "26") (pinfunction "RXCTL/PHYAD2_26") (pintype "passive"))
      (node (ref "R129") (pin "1") (pinfunction "1_1") (pintype "passive"))
      (node (ref "R167") (pin "2") (pinfunction "2_2") (pintype "passive"))
    )
    (net (code "39") (name "/PHY_TXCLK") (class "Default")
      (node (ref "D19") (pin "20") (pinfunction "TXC_20") (pintype "passive"))
      (node (ref "R141") (pin "1") (pinfunction "1_1") (pintype "passive"))
    )
    (net (code "40") (name "/PHY_TXD0") (class "Default")
      (node (ref "D19") (pin "18") (pinfunction "TXD0_18") (pintype "passive"))
      (node (ref "R124") (pin "1") (pinfunction "1_1") (pintype "passive"))
      (node (ref "R151") (pin "1") (pinfunction "1_1") (pintype "passive"))
    )
    (net (code "41") (name "/PHY_TXD1") (class "Default")
      (node (ref "D19") (pin "17") (pinfunction "TXD1_17") (pintype "passive"))
      (node (ref "R125") (pin "1") (pinfunction "1_1") (pintype "passive"))
      (node (ref "R154") (pin "1") (pinfunction "1_1") (pintype "passive"))
    )
    (net (code "42") (name "/PHY_TXD2") (class "Default")
      (node (ref "D19") (pin "16") (pinfunction "TXD2_16") (pintype "passive"))
      (node (ref "R120") (pin "1") (pinfunction "1_1") (pintype "passive"))
      (node (ref "R156") (pin "1") (pinfunction "1_1") (pintype "passive"))
    )
    (net (code "43") (name "/PHY_TXD3") (class "Default")
      (node (ref "D19") (pin "15") (pinfunction "TXD3_15") (pintype "passive"))
      (node (ref "R121") (pin "1") (pinfunction "1_1") (pintype "passive"))
      (node (ref "R157") (pin "1") (pinfunction "1_1") (pintype "passive"))
    )
    (net (code "44") (name "/PHY_TXEN") (class "Default")
      (node (ref "D19") (pin "19") (pinfunction "TXCTL_19") (pintype "passive"))
      (node (ref "R133") (pin "1") (pinfunction "1_1") (pintype "passive"))
    )
    (net (code "45") (name "/PHY_XTALIN") (class "Default")
      (node (ref "C339") (pin "1") (pinfunction "1_1") (pintype "power_in"))
      (node (ref "D19") (pin "36") (pinfunction "XTAL_IN_36") (pintype "passive"))
      (node (ref "Z4") (pin "1") (pinfunction "IN/OUT_1") (pintype "bidirectional"))
    )
    (net (code "46") (name "/PHY_XTALOUT") (class "Default")
      (node (ref "C340") (pin "1") (pinfunction "1_1") (pintype "power_in"))
      (node (ref "D19") (pin "37") (pinfunction "XTAL_OUT/EXT_CLK_37") (pintype "passive"))
      (node (ref "Z4") (pin "3") (pinfunction "IN/OUT_3") (pintype "bidirectional"))
    )
    (net (code "47") (name "/PoE_A") (class "Default")
      (node (ref "D20") (pin "24") (pinfunction "TCT_1_24") (pintype "passive"))
      (node (ref "J8") (pin "1") (pinfunction "1_1") (pintype "passive"))
      (node (ref "R139") (pin "1") (pinfunction "1_1") (pintype "passive"))
    )
    (net (code "48") (name "/PoE_B") (class "Default")
      (node (ref "D20") (pin "21") (pinfunction "TCT_2_21") (pintype "passive"))
      (node (ref "J8") (pin "2") (pinfunction "2_2") (pintype "passive"))
      (node (ref "R144") (pin "1") (pinfunction "1_1") (pintype "passive"))
    )
    (net (code "49") (name "/PoE_C") (class "Default")
      (node (ref "D20") (pin "18") (pinfunction "TCT_3_18") (pintype "passive"))
      (node (ref "J8") (pin "3") (pinfunction "3_3") (pintype "power_in"))
      (node (ref "R148") (pin "1") (pinfunction "1_1") (pintype "passive"))
    )
    (net (code "50") (name "/PoE_D") (class "Default")
      (node (ref "D20") (pin "15") (pinfunction "TCT_4_15") (pintype "passive"))
      (node (ref "J8") (pin "4") (pinfunction "4_4") (pintype "power_in"))
      (node (ref "R153") (pin "1") (pinfunction "1_1") (pintype "passive"))
    )
    (net (code "51") (name "/REG_OUT") (class "Default")
      (node (ref "C330") (pin "1") (pinfunction "1_1") (pintype "power_in"))
      (node (ref "D19") (pin "30") (pinfunction "REG_OUT/LDO_OUT_30") (pintype "passive"))
      (node (ref "L12") (pin "2") (pinfunction "2_2") (pintype "passive"))
      (node (ref "R119") (pin "1") (pinfunction "1_1") (pintype "passive"))
    )
    (net (code "52") (name "/RSET") (class "Default")
      (node (ref "D19") (pin "39") (pinfunction "RSET_39") (pintype "passive"))
      (node (ref "R128") (pin "1") (pinfunction "1_1") (pintype "passive"))
    )
    (net (code "53") (name "/TD0_N") (class "Default")
      (node (ref "D19") (pin "2") (pinfunction "MDIN0_2") (pintype "passive"))
      (node (ref "R140") (pin "1") (pinfunction "1_1") (pintype "passive"))
    )
    (net (code "54") (name "/TD0_P") (class "Default")
      (node (ref "D19") (pin "1") (pinfunction "MDIP0_1") (pintype "passive"))
      (node (ref "R137") (pin "1") (pinfunction "1_1") (pintype "passive"))
    )
    (net (code "55") (name "/TD1_N") (class "Default")
      (node (ref "D19") (pin "5") (pinfunction "MDIN1_5") (pintype "passive"))
      (node (ref "R145") (pin "1") (pinfunction "1_1") (pintype "passive"))
    )
    (net (code "56") (name "/TD1_P") (class "Default")
      (node (ref "D19") (pin "4") (pinfunction "MDIP1_4") (pintype "passive"))
      (node (ref "R142") (pin "1") (pinfunction "1_1") (pintype "passive"))
    )
    (net (code "57") (name "/TD2_N") (class "Default")
      (node (ref "D19") (pin "7") (pinfunction "MDIN2_7") (pintype "passive"))
      (node (ref "R149") (pin "1") (pinfunction "1_1") (pintype "passive"))
    )
    (net (code "58") (name "/TD2_P") (class "Default")
      (node (ref "D19") (pin "6") (pinfunction "MDIP2_6") (pintype "passive"))
      (node (ref "R146") (pin "1") (pinfunction "1_1") (pintype "passive"))
    )
    (net (code "59") (name "/TD3_N") (class "Default")
      (node (ref "D19") (pin "10") (pinfunction "MDIN3_10") (pintype "passive"))
      (node (ref "R155") (pin "1") (pinfunction "1_1") (pintype "passive"))
    )
    (net (code "60") (name "/TD3_P") (class "Default")
      (node (ref "D19") (pin "9") (pinfunction "MDIP3_9") (pintype "passive"))
      (node (ref "R150") (pin "1") (pinfunction "1_1") (pintype "passive"))
    )
    (net (code "61") (name "/TD_1_N") (class "Default")
      (node (ref "D20") (pin "3") (pinfunction "TD1-_3") (pintype "passive"))
      (node (ref "R140") (pin "2") (pinfunction "2_2") (pintype "passive"))
      (node (ref "VD25") (pin "2") (pinfunction "IN2_2") (pintype "passive"))
    )
    (net (code "62") (name "/TD_1_P") (class "Default")
      (node (ref "D20") (pin "2") (pinfunction "TD1+_2") (pintype "passive"))
      (node (ref "R137") (pin "2") (pinfunction "2_2") (pintype "passive"))
      (node (ref "VD25") (pin "1") (pinfunction "IN1_1") (pintype "passive"))
    )
    (net (code "63") (name "/TD_2_N") (class "Default")
      (node (ref "D20") (pin "6") (pinfunction "TD2-_6") (pintype "passive"))
      (node (ref "R145") (pin "2") (pinfunction "2_2") (pintype "passive"))
      (node (ref "VD25") (pin "5") (pinfunction "IN4_5") (pintype "passive"))
    )
    (net (code "64") (name "/TD_2_P") (class "Default")
      (node (ref "D20") (pin "5") (pinfunction "TD2+_5") (pintype "passive"))
      (node (ref "R142") (pin "2") (pinfunction "2_2") (pintype "passive"))
      (node (ref "VD25") (pin "4") (pinfunction "IN3_4") (pintype "passive"))
    )
    (net (code "65") (name "/TD_3_N") (class "Default")
      (node (ref "D20") (pin "9") (pinfunction "TD3-_9") (pintype "passive"))
      (node (ref "R149") (pin "2") (pinfunction "2_2") (pintype "passive"))
      (node (ref "VD26") (pin "2") (pinfunction "IN2_2") (pintype "passive"))
    )
    (net (code "66") (name "/TD_3_P") (class "Default")
      (node (ref "D20") (pin "8") (pinfunction "TD3+_8") (pintype "passive"))
      (node (ref "R146") (pin "2") (pinfunction "2_2") (pintype "passive"))
      (node (ref "VD26") (pin "1") (pinfunction "IN1_1") (pintype "passive"))
    )
    (net (code "67") (name "/TD_4_N") (class "Default")
      (node (ref "D20") (pin "12") (pinfunction "TD4-_12") (pintype "passive"))
      (node (ref "R155") (pin "2") (pinfunction "2_2") (pintype "passive"))
      (node (ref "VD26") (pin "5") (pinfunction "IN4_5") (pintype "passive"))
    )
    (net (code "68") (name "/TD_4_P") (class "Default")
      (node (ref "D20") (pin "11") (pinfunction "TD4+_11") (pintype "passive"))
      (node (ref "R150") (pin "2") (pinfunction "2_2") (pintype "passive"))
      (node (ref "VD26") (pin "4") (pinfunction "IN3_4") (pintype "passive"))
    )
    (net (code "69") (name "/VCC3V3_S3") (class "Default")
      (node (ref "C344") (pin "1") (pinfunction "1_1") (pintype "power_in"))
      (node (ref "U1") (pin "J23") (pinfunction "APIO1_VDD_J23") (pintype "passive"))
    )
    (net (code "70") (name "/VCCIO_PHY") (class "Default")
      (node (ref "C324") (pin "1") (pinfunction "1_1") (pintype "power_in"))
      (node (ref "C325") (pin "1") (pinfunction "1_1") (pintype "power_in"))
      (node (ref "C338") (pin "1") (pinfunction "1_1") (pintype "power_in"))
      (node (ref "D19") (pin "28") (pinfunction "DVDD_RG_28") (pintype "passive"))
      (node (ref "L13") (pin "1") (pinfunction "1_1") (pintype "passive"))
      (node (ref "R160") (pin "2") (pinfunction "2_2") (pintype "passive"))
      (node (ref "R161") (pin "2") (pinfunction "2_2") (pintype "passive"))
      (node (ref "R163") (pin "2") (pinfunction "2_2") (pintype "passive"))
      (node (ref "R165") (pin "2") (pinfunction "2_2") (pintype "passive"))
    )
    (net (code "71") (name "/VCC_1V8") (class "Default")
      (node (ref "C345") (pin "1") (pinfunction "1_1") (pintype "power_in"))
      (node (ref "U1") (pin "J22") (pinfunction "APIO1_VDDPST_J22") (pintype "passive"))
    )
    (net (code "72") (name "/VCC_LAN") (class "Default")
      (node (ref "C326") (pin "1") (pinfunction "1_1") (pintype "power_in"))
      (node (ref "C327") (pin "1") (pinfunction "1_1") (pintype "power_in"))
      (node (ref "C328") (pin "1") (pinfunction "1_1") (pintype "power_in"))
      (node (ref "C329") (pin "1") (pinfunction "1_1") (pintype "power_in"))
      (node (ref "C337") (pin "1") (pinfunction "1_1") (pintype "power_in"))
      (node (ref "D19") (pin "11") (pinfunction "AVDD33_11") (pintype "passive"))
      (node (ref "D19") (pin "29") (pinfunction "DVDD33_29") (pintype "passive"))
      (node (ref "D19") (pin "40") (pinfunction "AVDD33_40") (pintype "passive"))
      (node (ref "L13") (pin "2") (pinfunction "2_2") (pintype "passive"))
      (node (ref "R130") (pin "2") (pinfunction "2_2") (pintype "passive"))
      (node (ref "R151") (pin "2") (pinfunction "2_2") (pintype "passive"))
      (node (ref "R154") (pin "2") (pinfunction "2_2") (pintype "passive"))
      (node (ref "R156") (pin "2") (pinfunction "2_2") (pintype "passive"))
      (node (ref "R157") (pin "2") (pinfunction "2_2") (pintype "passive"))
      (node (ref "R158") (pin "2") (pinfunction "2_2") (pintype "passive"))
      (node (ref "R159") (pin "2") (pinfunction "2_2") (pintype "passive"))
    )
    (net (code "73") (name "/VDD10_EPHY") (class "Default")
      (node (ref "C331") (pin "1") (pinfunction "1_1") (pintype "power_in"))
      (node (ref "C332") (pin "1") (pinfunction "1_1") (pintype "power_in"))
      (node (ref "C333") (pin "1") (pinfunction "1_1") (pintype "power_in"))
      (node (ref "C334") (pin "1") (pinfunction "1_1") (pintype "power_in"))
      (node (ref "C335") (pin "1") (pinfunction "1_1") (pintype "power_in"))
      (node (ref "C336") (pin "1") (pinfunction "1_1") (pintype "power_in"))
      (node (ref "D19") (pin "21") (pinfunction "DVDD10_21") (pintype "passive"))
      (node (ref "D19") (pin "3") (pinfunction "AVDD10_3") (pintype "passive"))
      (node (ref "D19") (pin "38") (pinfunction "AVDD10_38") (pintype "passive"))
      (node (ref "D19") (pin "8") (pinfunction "AVDD10_8") (pintype "passive"))
      (node (ref "L12") (pin "1") (pinfunction "1_1") (pintype "passive"))
      (node (ref "R119") (pin "2") (pinfunction "2_2") (pintype "passive"))
    )
    (net (code "74") (name "Net-(C342-Pad1)") (class "Default")
      (node (ref "C342") (pin "1") (pinfunction "1_1") (pintype "power_in"))
      (node (ref "C343") (pin "1") (pinfunction "1_1") (pintype "power_in"))
      (node (ref "C346") (pin "1") (pinfunction "1_1") (pintype "power_in"))
      (node (ref "C348") (pin "1") (pinfunction "1_1") (pintype "power_in"))
      (node (ref "C349") (pin "2") (pinfunction "2_2") (pintype "power_in"))
    )
    (net (code "75") (name "Net-(C342-Pad2)") (class "Default")
      (node (ref "C342") (pin "2") (pinfunction "2_2") (pintype "power_in"))
      (node (ref "R139") (pin "2") (pinfunction "2_2") (pintype "passive"))
    )
    (net (code "76") (name "Net-(C343-Pad2)") (class "Default")
      (node (ref "C343") (pin "2") (pinfunction "2_2") (pintype "power_in"))
      (node (ref "R144") (pin "2") (pinfunction "2_2") (pintype "passive"))
    )
    (net (code "77") (name "Net-(C346-Pad2)") (class "Default")
      (node (ref "C346") (pin "2") (pinfunction "2_2") (pintype "power_in"))
      (node (ref "R148") (pin "2") (pinfunction "2_2") (pintype "passive"))
    )
    (net (code "78") (name "Net-(C347-Pad1)") (class "Default")
      (node (ref "C347") (pin "1") (pinfunction "1_1") (pintype "power_in"))
      (node (ref "R138") (pin "2") (pinfunction "2_2") (pintype "passive"))
      (node (ref "R143") (pin "2") (pinfunction "2_2") (pintype "passive"))
      (node (ref "R147") (pin "2") (pinfunction "2_2") (pintype "passive"))
      (node (ref "R152") (pin "2") (pinfunction "2_2") (pintype "passive"))
    )
    (net (code "79") (name "Net-(C348-Pad2)") (class "Default")
      (node (ref "C348") (pin "2") (pinfunction "2_2") (pintype "power_in"))
      (node (ref "R153") (pin "2") (pinfunction "2_2") (pintype "passive"))
    )
    (net (code "80") (name "Net-(D20-TCT1)") (class "Default")
      (node (ref "D20") (pin "1") (pinfunction "TCT1_1") (pintype "passive"))
      (node (ref "R138") (pin "1") (pinfunction "1_1") (pintype "passive"))
    )
    (net (code "81") (name "Net-(D20-TCT2)") (class "Default")
      (node (ref "D20") (pin "4") (pinfunction "TCT2_4") (pintype "passive"))
      (node (ref "R143") (pin "1") (pinfunction "1_1") (pintype "passive"))
    )
    (net (code "82") (name "Net-(D20-TCT3)") (class "Default")
      (node (ref "D20") (pin "7") (pinfunction "TCT3_7") (pintype "passive"))
      (node (ref "R147") (pin "1") (pinfunction "1_1") (pintype "passive"))
    )
    (net (code "83") (name "Net-(D20-TCT4)") (class "Default")
      (node (ref "D20") (pin "10") (pinfunction "TCT4_10") (pintype "passive"))
      (node (ref "R152") (pin "1") (pinfunction "1_1") (pintype "passive"))
    )
    (net (code "84") (name "Net-(J7-LED_GREEN-)") (class "Default")
      (node (ref "J7") (pin "9") (pinfunction "LED_GREEN-_9") (pintype "passive"))
      (node (ref "R166") (pin "1") (pinfunction "1_1") (pintype "passive"))
    )
    (net (code "85") (name "Net-(J7-LED_YELLOW-)") (class "Default")
      (node (ref "J7") (pin "11") (pinfunction "LED_YELLOW-_11") (pintype "passive"))
      (node (ref "R169") (pin "1") (pinfunction "1_1") (pintype "passive"))
    )
  )
)
